# attiny85-ws2812b-v2.net
KiCad netlist of a schematic drawn in EAGLE
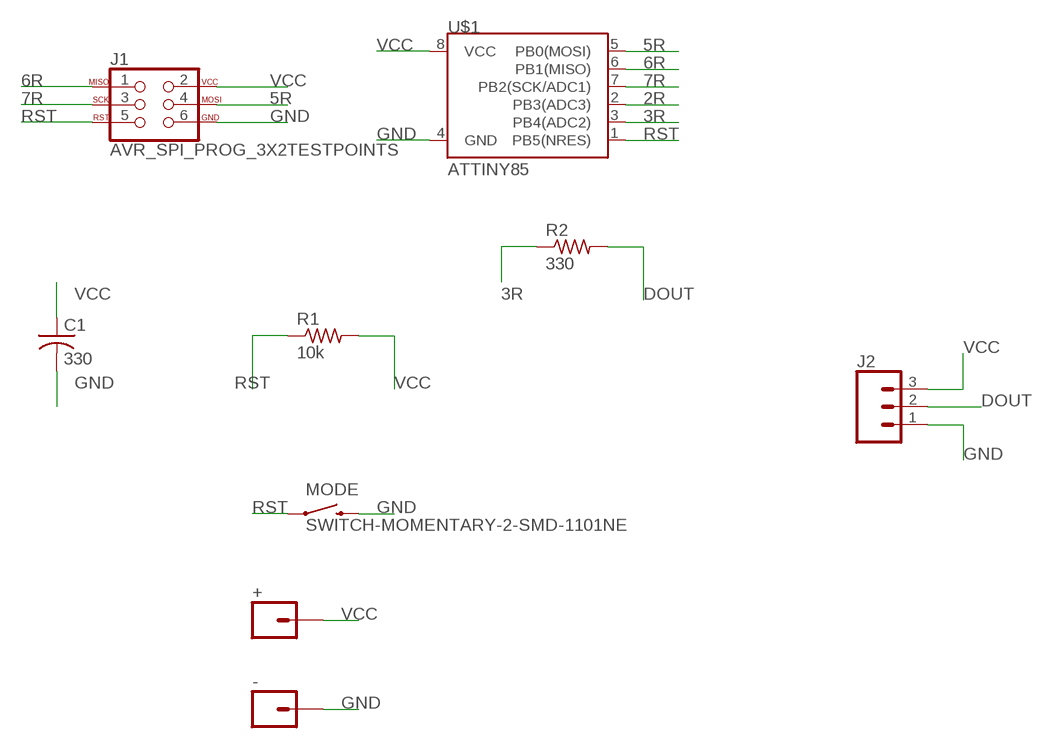
[diagram p0: schematic, sheet 1]

(export (version "E")
  (design (tool "Eeschema 10.0.6"))
  (components
    (comp (ref "+")
      (value "CONN_01PTH_NO_SILK_YES_STOP")
      (footprint "eagle-import:1X01_NO_SILK")
      (libsource (lib "eagle-import") (part "CONN_01PTH_NO_SILK_YES_STOP"))
    )
    (comp (ref "-")
      (value "CONN_01PTH_NO_SILK_YES_STOP")
      (footprint "eagle-import:1X01_NO_SILK")
      (libsource (lib "eagle-import") (part "CONN_01PTH_NO_SILK_YES_STOP"))
    )
    (comp (ref "C1")
      (value "330")
      (footprint "eagle-import:C0603")
      (libsource (lib "eagle-import") (part "C-USC0603"))
    )
    (comp (ref "J1")
      (value "AVR_SPI_PROG_3X2TESTPOINTS")
      (footprint "eagle-import:2X3_TEST_POINTS")
      (libsource (lib "eagle-import") (part "AVR_SPI_PROG_3X2TESTPOINTS"))
    )
    (comp (ref "J2")
      (value "CONN_031X03_NO_SILK")
      (footprint "eagle-import:1X03_NO_SILK")
      (libsource (lib "eagle-import") (part "CONN_031X03_NO_SILK"))
    )
    (comp (ref "MODE")
      (value "SWITCH-MOMENTARY-2-SMD-1101NE")
      (footprint "eagle-import:TACTILE-SWITCH-1101NE")
      (libsource (lib "eagle-import") (part "SWITCH-MOMENTARY-2-SMD-1101NE"))
    )
    (comp (ref "R1")
      (value "10k")
      (footprint "eagle-import:R0603")
      (libsource (lib "eagle-import") (part "resistor_348_R-US_R0603"))
    )
    (comp (ref "R2")
      (value "330")
      (footprint "eagle-import:R0603")
      (libsource (lib "eagle-import") (part "R-US_R0603"))
    )
    (comp (ref "U$1")
      (value "ATTINY85")
      (footprint "eagle-import:SO08-EIAJ")
      (libsource (lib "eagle-import") (part "ATTINY45"))
    )
  )
  (nets
    (net (code "1") (name "/2R") (class "Default")
      (node (ref "U$1") (pin "2") (pinfunction "PB3(ADC3)_2") (pintype "bidirectional"))
    )
    (net (code "2") (name "/3R") (class "Default")
      (node (ref "R2") (pin "1") (pinfunction "1_1") (pintype "passive"))
      (node (ref "U$1") (pin "3") (pinfunction "PB4(ADC2)_3") (pintype "bidirectional"))
    )
    (net (code "3") (name "/5R") (class "Default")
      (node (ref "J1") (pin "4") (pinfunction "4_4") (pintype "passive"))
      (node (ref "U$1") (pin "5") (pinfunction "PB0(MOSI)_5") (pintype "bidirectional"))
    )
    (net (code "4") (name "/6R") (class "Default")
      (node (ref "J1") (pin "1") (pinfunction "1_1") (pintype "passive"))
      (node (ref "U$1") (pin "6") (pinfunction "PB1(MISO)_6") (pintype "bidirectional"))
    )
    (net (code "5") (name "/7R") (class "Default")
      (node (ref "J1") (pin "3") (pinfunction "3_3") (pintype "passive"))
      (node (ref "U$1") (pin "7") (pinfunction "PB2(SCK/ADC1)_7") (pintype "bidirectional"))
    )
    (net (code "6") (name "/DOUT") (class "Default")
      (node (ref "J2") (pin "2") (pinfunction "2_2") (pintype "passive"))
      (node (ref "R2") (pin "2") (pinfunction "2_2") (pintype "passive"))
    )
    (net (code "7") (name "/GND") (class "Default")
      (node (ref "-") (pin "1") (pinfunction "1_1") (pintype "passive"))
      (node (ref "C1") (pin "2") (pinfunction "2_2") (pintype "passive"))
      (node (ref "J1") (pin "6") (pinfunction "6_6") (pintype "passive"))
      (node (ref "J2") (pin "1") (pinfunction "1_1") (pintype "passive"))
      (node (ref "MODE") (pin "P$2") (pinfunction "2_P$2") (pintype "passive"))
      (node (ref "U$1") (pin "4") (pinfunction "GND_4") (pintype "bidirectional"))
    )
    (net (code "8") (name "/RST") (class "Default")
      (node (ref "J1") (pin "5") (pinfunction "5_5") (pintype "passive"))
      (node (ref "MODE") (pin "P$1") (pinfunction "1_P$1") (pintype "passive"))
      (node (ref "R1") (pin "1") (pinfunction "1_1") (pintype "passive"))
      (node (ref "U$1") (pin "1") (pinfunction "PB5(NRES)_1") (pintype "bidirectional"))
    )
    (net (code "9") (name "/VCC") (class "Default")
      (node (ref "+") (pin "1") (pinfunction "1_1") (pintype "passive"))
      (node (ref "C1") (pin "1") (pinfunction "1_1") (pintype "passive"))
      (node (ref "J1") (pin "2") (pinfunction "2_2") (pintype "passive"))
      (node (ref "J2") (pin "3") (pinfunction "3_3") (pintype "passive"))
      (node (ref "R1") (pin "2") (pinfunction "2_2") (pintype "passive"))
      (node (ref "U$1") (pin "8") (pinfunction "VCC_8") (pintype "bidirectional"))
    )
  )
)
